# Solder_Training_Tier_3.net
KiCad netlist of a schematic drawn in Altium Designer
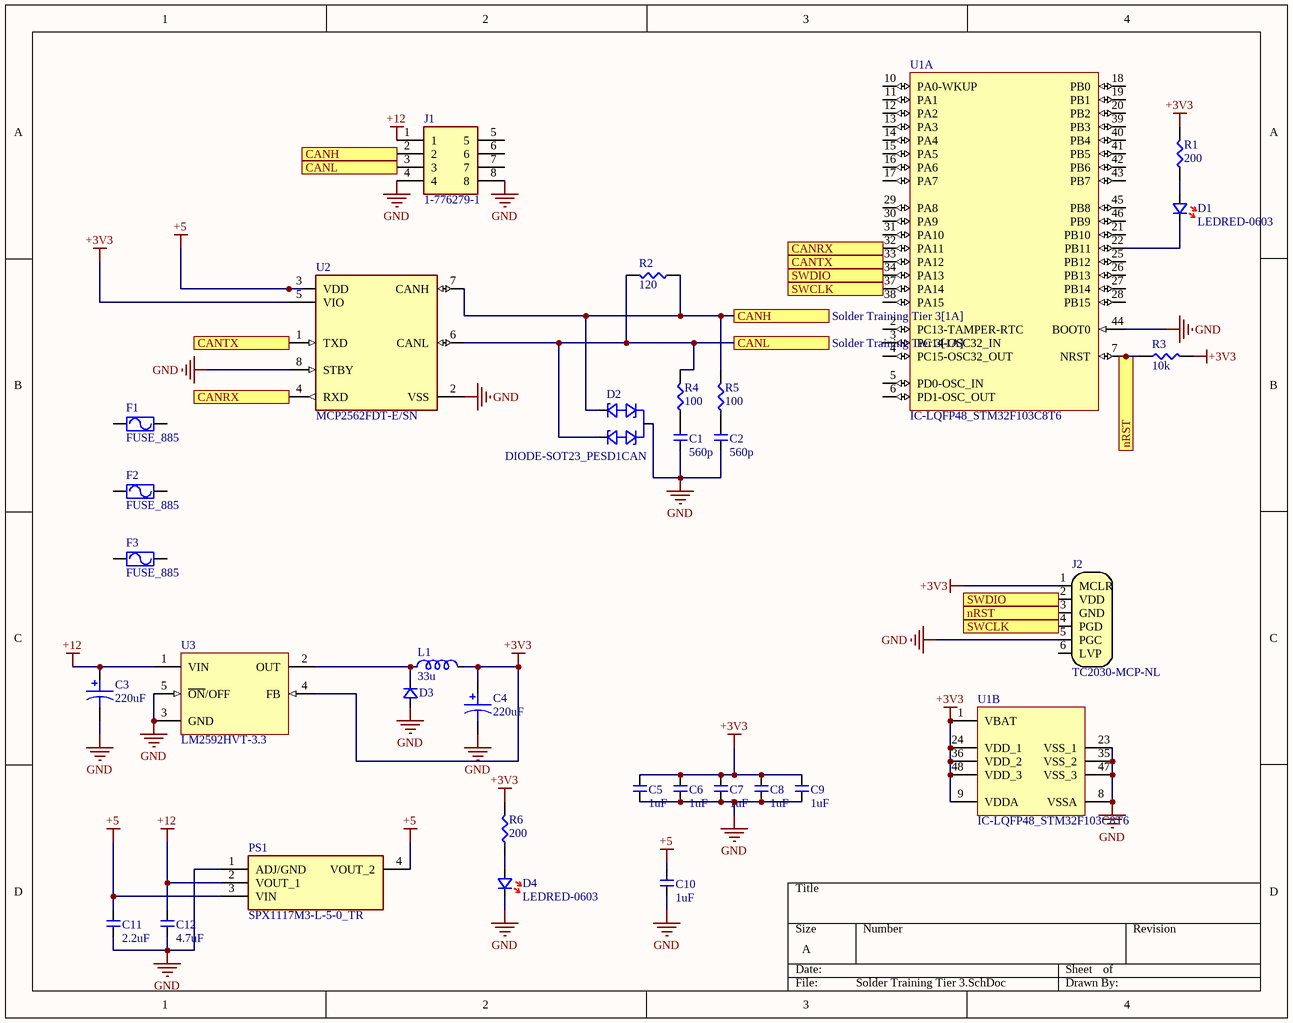
[diagram p0: Solder Training Tier 3.SchDoc]

(export (version "E")
  (design (tool "Eeschema 10.0.6"))
  (components
    (comp (ref "C1")
      (value "560p")
      (footprint "CAP-0603")
      (fields (field (name "SOURCE") "ife19_Elec_Library.SchLib"))
      (libsource (lib "Illini Formula Electric") (part "CAP-0603"))
    )
    (comp (ref "C2")
      (value "560p")
      (footprint "CAP-0603")
      (fields (field (name "SOURCE") "ife19_Elec_Library.SchLib"))
      (libsource (lib "Illini Formula Electric") (part "CAP-0603"))
    )
    (comp (ref "C3")
      (value "220uF")
      (footprint "CAP-6.3D7.7H-SMD")
      (fields (field (name "SOURCE") "ife19_Elec_Library.SchLib"))
      (libsource (lib "Illini Formula Electric") (part "CAP-6.3D7.7H-SMD"))
    )
    (comp (ref "C4")
      (value "220uF")
      (footprint "CAP-6.3D7.7H-SMD")
      (fields (field (name "SOURCE") "ife19_Elec_Library.SchLib"))
      (libsource (lib "Illini Formula Electric") (part "CAP-6.3D7.7H-SMD"))
    )
    (comp (ref "C5")
      (value "1uF")
      (footprint "CAP-0603")
      (fields (field (name "SOURCE") "ife19_Elec_Library.SchLib"))
      (libsource (lib "Illini Formula Electric") (part "CAP-0603"))
    )
    (comp (ref "C6")
      (value "1uF")
      (footprint "CAP-0603")
      (fields (field (name "SOURCE") "ife19_Elec_Library.SchLib"))
      (libsource (lib "Illini Formula Electric") (part "CAP-0603"))
    )
    (comp (ref "C7")
      (value "1uF")
      (footprint "CAP-0603")
      (fields (field (name "SOURCE") "ife19_Elec_Library.SchLib"))
      (libsource (lib "Illini Formula Electric") (part "CAP-0603"))
    )
    (comp (ref "C8")
      (value "1uF")
      (footprint "CAP-0603")
      (fields (field (name "SOURCE") "ife19_Elec_Library.SchLib"))
      (libsource (lib "Illini Formula Electric") (part "CAP-0603"))
    )
    (comp (ref "C9")
      (value "1uF")
      (footprint "CAP-0603")
      (fields (field (name "SOURCE") "ife19_Elec_Library.SchLib"))
      (libsource (lib "Illini Formula Electric") (part "CAP-0603"))
    )
    (comp (ref "C10")
      (value "1uF")
      (footprint "CAP-0603")
      (fields (field (name "SOURCE") "ife19_Elec_Library.SchLib"))
      (libsource (lib "Illini Formula Electric") (part "CAP-0603"))
    )
    (comp (ref "C11")
      (value "2.2uF")
      (footprint "CAP-0603")
      (fields (field (name "SOURCE") "ife19_Elec_Library.SchLib"))
      (libsource (lib "Illini Formula Electric") (part "CAP-0603"))
    )
    (comp (ref "C12")
      (value "4.7uF")
      (footprint "CAP-0603")
      (fields (field (name "SOURCE") "ife19_Elec_Library.SchLib"))
      (libsource (lib "Illini Formula Electric") (part "CAP-0603"))
    )
    (comp (ref "D1")
      (value "LEDRED-0603")
      (footprint "LEDRED-0603")
      (fields (field (name "SOURCE") "ife19_Elec_Library.SchLib"))
      (libsource (lib "") (part "Symbol_3"))
    )
    (comp (ref "D2")
      (value "DIODE-SOT23_PESD1CAN")
      (footprint "SOT23")
      (fields (field (name "SOURCE") "ife19_Elec_Library.SchLib"))
      (libsource (lib "Illini Formula Electric") (part "DIODE-SOT23_PESD1CAN"))
    )
    (comp (ref "D3")
      (value "~")
      (footprint "SOD123")
      (fields (field (name "SOURCE") "ife19_Elec_Library.SchLib"))
      (libsource (lib "") (part "Symbol_4"))
    )
    (comp (ref "D4")
      (value "LEDRED-0603")
      (footprint "LEDRED-0603")
      (fields (field (name "SOURCE") "ife19_Elec_Library.SchLib"))
      (libsource (lib "") (part "Symbol_3"))
    )
    (comp (ref "F1")
      (value "FUSE_885")
      (footprint "FUSE_885")
      (fields (field (name "SOURCE") "ife19_Elec_Library.SchLib"))
      (libsource (lib "") (part "Symbol_1"))
    )
    (comp (ref "F2")
      (value "FUSE_885")
      (footprint "FUSE_885")
      (fields (field (name "SOURCE") "ife19_Elec_Library.SchLib"))
      (libsource (lib "") (part "Symbol_1"))
    )
    (comp (ref "F3")
      (value "FUSE_885")
      (footprint "FUSE_885")
      (fields (field (name "SOURCE") "ife19_Elec_Library.SchLib"))
      (libsource (lib "") (part "Symbol_1"))
    )
    (comp (ref "J1")
      (value "1-776279-1")
      (footprint "17762791")
      (description "Connector")
      (fields (field (name "MOUSER PART NUMBER") "571-1-776279-1"))
      (libsource (lib "Illini Formula Electric") (part "1-776279-1"))
    )
    (comp (ref "J2")
      (value "TC2030-MCP-NL")
      (footprint "TC2030-MCP-NL")
      (description "Conector par ICD")
      (fields (field (name "SOURCE") "Image Pasted at 2021-10-31 17-08.SchLib"))
      (libsource (lib "Illini Formula Electric") (part "TC2030-MCP-NL"))
    )
    (comp (ref "L1")
      (value "33u")
      (footprint "IND-6045")
      (fields (field (name "SOURCE") "ife19_Elec_Library.SchLib"))
      (libsource (lib "Illini Formula Electric") (part "Symbol"))
    )
    (comp (ref "PS1")
      (value "SPX1117M3-L-5-0_TR")
      (footprint "SOT230P700X170-4N")
      (description "Power Supply")
      (fields
        (field (name "ARROW PART NUMBER") "SPX1117M3-L-5-0/TR")
        (field (name "MOUSER PART NUMBER") "701-SPX1117M3-L-50TR")
      )
      (libsource (lib "Illini Formula Electric") (part "SPX1117M3-L-5-0_TR"))
    )
    (comp (ref "R1")
      (value "200")
      (footprint "RES-0603")
      (fields (field (name "SOURCE") "ife19_Elec_Library.SchLib"))
      (libsource (lib "") (part "Symbol_2"))
    )
    (comp (ref "R2")
      (value "120")
      (footprint "RES-0603")
      (fields (field (name "SOURCE") "ife19_Elec_Library.SchLib"))
      (libsource (lib "") (part "Symbol_2"))
    )
    (comp (ref "R3")
      (value "10k")
      (footprint "RES-0603")
      (fields (field (name "SOURCE") "ife19_Elec_Library.schlib"))
      (libsource (lib "") (part "Symbol_2"))
    )
    (comp (ref "R4")
      (value "100")
      (footprint "RES-0603")
      (fields (field (name "SOURCE") "ife19_Elec_Library.SchLib"))
      (libsource (lib "") (part "Symbol_2"))
    )
    (comp (ref "R5")
      (value "100")
      (footprint "RES-0603")
      (fields (field (name "SOURCE") "ife19_Elec_Library.SchLib"))
      (libsource (lib "") (part "Symbol_2"))
    )
    (comp (ref "R6")
      (value "200")
      (footprint "RES-0603")
      (fields (field (name "SOURCE") "ife19_Elec_Library.SchLib"))
      (libsource (lib "") (part "Symbol_2"))
    )
    (comp (ref "U1")
      (value "IC-LQFP48_STM32F103C8T6")
      (footprint "STM-LQFP48_M")
      (fields (field (name "PARTNUMBER") "STM32F103C8T6") (field (name "SOURCE") "ife19_Elec_Library.SchLib"))
      (libsource (lib "Illini Formula Electric") (part "IC-LQFP48_STM32F103C8T6"))
    )
    (comp (ref "U2")
      (value "MCP2562FDT-E/SN")
      (footprint "FP-C04-057-SN-MFG")
      (description "IC TRANSCEIVER 1/1 8SOIC")
      (libsource (lib "Altium Content Vault") (part "fcb6c66e4429206983adab9201371df"))
    )
    (comp (ref "U3")
      (value "LM2592HVT-3.3")
      (footprint "T05D")
      (description "SIMPLE SWITCHER® Power Converter 150 KHz 2A Step-Down Voltage Regulator, 5-pin TO-220")
      (fields (field (name "MANUFACTURER") "National Semiconductor"))
      (libsource (lib "Altium Content Vault") (part "PM-REG-LM2575HVT-12"))
    )
  )
  (nets
    (net (code "1") (name "+3V3") (class "Default")
      (node (ref "C4") (pin "POS") (pinfunction "+_POS") (pintype "passive"))
      (node (ref "C5") (pin "2") (pinfunction "2_2") (pintype "passive"))
      (node (ref "C6") (pin "2") (pinfunction "2_2") (pintype "passive"))
      (node (ref "C7") (pin "2") (pinfunction "2_2") (pintype "passive"))
      (node (ref "C8") (pin "2") (pinfunction "2_2") (pintype "passive"))
      (node (ref "C9") (pin "2") (pinfunction "2_2") (pintype "passive"))
      (node (ref "J2") (pin "1") (pinfunction "MCLR_1") (pintype "passive"))
      (node (ref "L1") (pin "2") (pinfunction "2_2") (pintype "passive"))
      (node (ref "R1") (pin "2") (pinfunction "2_2") (pintype "passive"))
      (node (ref "R3") (pin "2") (pinfunction "2_2") (pintype "passive"))
      (node (ref "R6") (pin "2") (pinfunction "2_2") (pintype "passive"))
      (node (ref "U1") (pin "1") (pinfunction "VBAT_1") (pintype "power_in"))
      (node (ref "U1") (pin "24") (pinfunction "VDD_1_24") (pintype "power_in"))
      (node (ref "U1") (pin "36") (pinfunction "VDD_2_36") (pintype "power_in"))
      (node (ref "U1") (pin "48") (pinfunction "VDD_3_48") (pintype "power_in"))
      (node (ref "U1") (pin "9") (pinfunction "VDDA_9") (pintype "power_in"))
      (node (ref "U2") (pin "5") (pinfunction "VIO_5") (pintype "power_in"))
      (node (ref "U3") (pin "4") (pinfunction "FB_4") (pintype "input"))
    )
    (net (code "2") (name "+5") (class "Default")
      (node (ref "C10") (pin "2") (pinfunction "2_2") (pintype "passive"))
      (node (ref "C11") (pin "2") (pinfunction "2_2") (pintype "passive"))
      (node (ref "PS1") (pin "3") (pinfunction "VIN_3") (pintype "passive"))
      (node (ref "PS1") (pin "4") (pinfunction "VOUT_2_4") (pintype "passive"))
      (node (ref "U2") (pin "3") (pinfunction "VDD_3") (pintype "power_in"))
    )
    (net (code "3") (name "+12") (class "Default")
      (node (ref "C12") (pin "2") (pinfunction "2_2") (pintype "passive"))
      (node (ref "C3") (pin "POS") (pinfunction "+_POS") (pintype "passive"))
      (node (ref "J1") (pin "1") (pinfunction "1_1") (pintype "passive"))
      (node (ref "PS1") (pin "2") (pinfunction "VOUT_1_2") (pintype "passive"))
      (node (ref "U3") (pin "1") (pinfunction "VIN_1") (pintype "power_in"))
    )
    (net (code "4") (name "/CANH") (class "Default")
      (node (ref "D2") (pin "1") (pinfunction "CAN1_1") (pintype "passive"))
      (node (ref "J1") (pin "2") (pinfunction "2_2") (pintype "passive"))
      (node (ref "R2") (pin "1") (pinfunction "1_1") (pintype "passive"))
      (node (ref "R5") (pin "2") (pinfunction "2_2") (pintype "passive"))
      (node (ref "U2") (pin "7") (pinfunction "CANH_7") (pintype "bidirectional"))
    )
    (net (code "5") (name "/CANL") (class "Default")
      (node (ref "D2") (pin "2") (pinfunction "CAN2_2") (pintype "passive"))
      (node (ref "J1") (pin "3") (pinfunction "3_3") (pintype "passive"))
      (node (ref "R2") (pin "2") (pinfunction "2_2") (pintype "passive"))
      (node (ref "R4") (pin "2") (pinfunction "2_2") (pintype "passive"))
      (node (ref "U2") (pin "6") (pinfunction "CANL_6") (pintype "bidirectional"))
    )
    (net (code "6") (name "/CANRX") (class "Default")
      (node (ref "U1") (pin "32") (pinfunction "PA11_32") (pintype "bidirectional"))
      (node (ref "U2") (pin "4") (pinfunction "RXD_4") (pintype "output"))
    )
    (net (code "7") (name "/CANTX") (class "Default")
      (node (ref "U1") (pin "33") (pinfunction "PA12_33") (pintype "bidirectional"))
      (node (ref "U2") (pin "1") (pinfunction "TXD_1") (pintype "input"))
    )
    (net (code "8") (name "/SWCLK") (class "Default")
      (node (ref "J2") (pin "4") (pinfunction "PGD_4") (pintype "passive"))
      (node (ref "U1") (pin "37") (pinfunction "PA14_37") (pintype "bidirectional"))
    )
    (net (code "9") (name "/SWDIO") (class "Default")
      (node (ref "J2") (pin "2") (pinfunction "VDD_2") (pintype "passive"))
      (node (ref "U1") (pin "34") (pinfunction "PA13_34") (pintype "bidirectional"))
    )
    (net (code "10") (name "/nRST") (class "Default")
      (node (ref "J2") (pin "3") (pinfunction "GND_3") (pintype "passive"))
      (node (ref "R3") (pin "1") (pinfunction "1_1") (pintype "passive"))
      (node (ref "U1") (pin "7") (pinfunction "NRST_7") (pintype "bidirectional"))
    )
    (net (code "11") (name "GND") (class "Default")
      (node (ref "C1") (pin "1") (pinfunction "1_1") (pintype "passive"))
      (node (ref "C10") (pin "1") (pinfunction "1_1") (pintype "passive"))
      (node (ref "C11") (pin "1") (pinfunction "1_1") (pintype "passive"))
      (node (ref "C12") (pin "1") (pinfunction "1_1") (pintype "passive"))
      (node (ref "C2") (pin "1") (pinfunction "1_1") (pintype "passive"))
      (node (ref "C3") (pin "NEG") (pinfunction "-_NEG") (pintype "passive"))
      (node (ref "C4") (pin "NEG") (pinfunction "-_NEG") (pintype "passive"))
      (node (ref "C5") (pin "1") (pinfunction "1_1") (pintype "passive"))
      (node (ref "C6") (pin "1") (pinfunction "1_1") (pintype "passive"))
      (node (ref "C7") (pin "1") (pinfunction "1_1") (pintype "passive"))
      (node (ref "C8") (pin "1") (pinfunction "1_1") (pintype "passive"))
      (node (ref "C9") (pin "1") (pinfunction "1_1") (pintype "passive"))
      (node (ref "D2") (pin "3") (pinfunction "G_3") (pintype "passive"))
      (node (ref "D3") (pin "A") (pinfunction "A_A") (pintype "passive"))
      (node (ref "D4") (pin "K") (pinfunction "K_K") (pintype "passive"))
      (node (ref "J1") (pin "4") (pinfunction "4_4") (pintype "passive"))
      (node (ref "J1") (pin "8") (pinfunction "8_8") (pintype "passive"))
      (node (ref "J2") (pin "5") (pinfunction "PGC_5") (pintype "passive"))
      (node (ref "PS1") (pin "1") (pinfunction "ADJ/GND_1") (pintype "passive"))
      (node (ref "U1") (pin "23") (pinfunction "VSS_1_23") (pintype "power_in"))
      (node (ref "U1") (pin "35") (pinfunction "VSS_2_35") (pintype "power_in"))
      (node (ref "U1") (pin "44") (pinfunction "BOOT0_44") (pintype "input"))
      (node (ref "U1") (pin "47") (pinfunction "VSS_3_47") (pintype "power_in"))
      (node (ref "U1") (pin "8") (pinfunction "VSSA_8") (pintype "power_in"))
      (node (ref "U2") (pin "2") (pinfunction "VSS_2") (pintype "power_in"))
      (node (ref "U2") (pin "8") (pinfunction "STBY_8") (pintype "input"))
      (node (ref "U3") (pin "3") (pinfunction "GND_3") (pintype "power_in"))
      (node (ref "U3") (pin "5") (pinfunction "~{ON}/OFF_5") (pintype "input"))
    )
    (net (code "12") (name "Net-(C1-Pad2)") (class "Default")
      (node (ref "C1") (pin "2") (pinfunction "2_2") (pintype "passive"))
      (node (ref "R4") (pin "1") (pinfunction "1_1") (pintype "passive"))
    )
    (net (code "13") (name "Net-(C2-Pad2)") (class "Default")
      (node (ref "C2") (pin "2") (pinfunction "2_2") (pintype "passive"))
      (node (ref "R5") (pin "1") (pinfunction "1_1") (pintype "passive"))
    )
    (net (code "14") (name "Net-(D1-PadA)") (class "Default")
      (node (ref "D1") (pin "A") (pinfunction "A_A") (pintype "passive"))
      (node (ref "R1") (pin "1") (pinfunction "1_1") (pintype "passive"))
    )
    (net (code "15") (name "Net-(D4-PadA)") (class "Default")
      (node (ref "D4") (pin "A") (pinfunction "A_A") (pintype "passive"))
      (node (ref "R6") (pin "1") (pinfunction "1_1") (pintype "passive"))
    )
    (net (code "16") (name "Net-(U1A-PB11)") (class "Default")
      (node (ref "D1") (pin "K") (pinfunction "K_K") (pintype "passive"))
      (node (ref "U1") (pin "22") (pinfunction "PB11_22") (pintype "bidirectional"))
    )
    (net (code "17") (name "Net-(U3-OUT)") (class "Default")
      (node (ref "D3") (pin "K") (pinfunction "K_K") (pintype "passive"))
      (node (ref "L1") (pin "1") (pinfunction "1_1") (pintype "passive"))
      (node (ref "U3") (pin "2") (pinfunction "OUT_2") (pintype "power_in"))
    )
    (net (code "18") (name "unconnected-(F1-Pad1)") (class "Default")
      (node (ref "F1") (pin "1") (pinfunction "1_1") (pintype "passive"))
    )
    (net (code "19") (name "unconnected-(F1-Pad2)") (class "Default")
      (node (ref "F1") (pin "2") (pinfunction "2_2") (pintype "passive"))
    )
    (net (code "20") (name "unconnected-(F2-Pad1)") (class "Default")
      (node (ref "F2") (pin "1") (pinfunction "1_1") (pintype "passive"))
    )
    (net (code "21") (name "unconnected-(F2-Pad2)") (class "Default")
      (node (ref "F2") (pin "2") (pinfunction "2_2") (pintype "passive"))
    )
    (net (code "22") (name "unconnected-(F3-Pad1)") (class "Default")
      (node (ref "F3") (pin "1") (pinfunction "1_1") (pintype "passive"))
    )
    (net (code "23") (name "unconnected-(F3-Pad2)") (class "Default")
      (node (ref "F3") (pin "2") (pinfunction "2_2") (pintype "passive"))
    )
    (net (code "24") (name "unconnected-(J1-Pad5)") (class "Default")
      (node (ref "J1") (pin "5") (pinfunction "5_5") (pintype "passive"))
    )
    (net (code "25") (name "unconnected-(J1-Pad6)") (class "Default")
      (node (ref "J1") (pin "6") (pinfunction "6_6") (pintype "passive"))
    )
    (net (code "26") (name "unconnected-(J1-Pad7)") (class "Default")
      (node (ref "J1") (pin "7") (pinfunction "7_7") (pintype "passive"))
    )
    (net (code "27") (name "unconnected-(J2-LVP-Pad6)") (class "Default")
      (node (ref "J2") (pin "6") (pinfunction "LVP_6") (pintype "passive"))
    )
    (net (code "28") (name "unconnected-(U1A-PA0-WKUP-Pad10)") (class "Default")
      (node (ref "U1") (pin "10") (pinfunction "PA0-WKUP_10") (pintype "bidirectional"))
    )
    (net (code "29") (name "unconnected-(U1A-PA1-Pad11)") (class "Default")
      (node (ref "U1") (pin "11") (pinfunction "PA1_11") (pintype "bidirectional"))
    )
    (net (code "30") (name "unconnected-(U1A-PA2-Pad12)") (class "Default")
      (node (ref "U1") (pin "12") (pinfunction "PA2_12") (pintype "bidirectional"))
    )
    (net (code "31") (name "unconnected-(U1A-PA3-Pad13)") (class "Default")
      (node (ref "U1") (pin "13") (pinfunction "PA3_13") (pintype "bidirectional"))
    )
    (net (code "32") (name "unconnected-(U1A-PA4-Pad14)") (class "Default")
      (node (ref "U1") (pin "14") (pinfunction "PA4_14") (pintype "bidirectional"))
    )
    (net (code "33") (name "unconnected-(U1A-PA5-Pad15)") (class "Default")
      (node (ref "U1") (pin "15") (pinfunction "PA5_15") (pintype "bidirectional"))
    )
    (net (code "34") (name "unconnected-(U1A-PA6-Pad16)") (class "Default")
      (node (ref "U1") (pin "16") (pinfunction "PA6_16") (pintype "bidirectional"))
    )
    (net (code "35") (name "unconnected-(U1A-PA7-Pad17)") (class "Default")
      (node (ref "U1") (pin "17") (pinfunction "PA7_17") (pintype "bidirectional"))
    )
    (net (code "36") (name "unconnected-(U1A-PA8-Pad29)") (class "Default")
      (node (ref "U1") (pin "29") (pinfunction "PA8_29") (pintype "bidirectional"))
    )
    (net (code "37") (name "unconnected-(U1A-PA9-Pad30)") (class "Default")
      (node (ref "U1") (pin "30") (pinfunction "PA9_30") (pintype "bidirectional"))
    )
    (net (code "38") (name "unconnected-(U1A-PA10-Pad31)") (class "Default")
      (node (ref "U1") (pin "31") (pinfunction "PA10_31") (pintype "bidirectional"))
    )
    (net (code "39") (name "unconnected-(U1A-PA15-Pad38)") (class "Default")
      (node (ref "U1") (pin "38") (pinfunction "PA15_38") (pintype "bidirectional"))
    )
    (net (code "40") (name "unconnected-(U1A-PB0-Pad18)") (class "Default")
      (node (ref "U1") (pin "18") (pinfunction "PB0_18") (pintype "bidirectional"))
    )
    (net (code "41") (name "unconnected-(U1A-PB1-Pad19)") (class "Default")
      (node (ref "U1") (pin "19") (pinfunction "PB1_19") (pintype "bidirectional"))
    )
    (net (code "42") (name "unconnected-(U1A-PB2-Pad20)") (class "Default")
      (node (ref "U1") (pin "20") (pinfunction "PB2_20") (pintype "bidirectional"))
    )
    (net (code "43") (name "unconnected-(U1A-PB3-Pad39)") (class "Default")
      (node (ref "U1") (pin "39") (pinfunction "PB3_39") (pintype "bidirectional"))
    )
    (net (code "44") (name "unconnected-(U1A-PB4-Pad40)") (class "Default")
      (node (ref "U1") (pin "40") (pinfunction "PB4_40") (pintype "bidirectional"))
    )
    (net (code "45") (name "unconnected-(U1A-PB5-Pad41)") (class "Default")
      (node (ref "U1") (pin "41") (pinfunction "PB5_41") (pintype "bidirectional"))
    )
    (net (code "46") (name "unconnected-(U1A-PB6-Pad42)") (class "Default")
      (node (ref "U1") (pin "42") (pinfunction "PB6_42") (pintype "bidirectional"))
    )
    (net (code "47") (name "unconnected-(U1A-PB7-Pad43)") (class "Default")
      (node (ref "U1") (pin "43") (pinfunction "PB7_43") (pintype "bidirectional"))
    )
    (net (code "48") (name "unconnected-(U1A-PB8-Pad45)") (class "Default")
      (node (ref "U1") (pin "45") (pinfunction "PB8_45") (pintype "bidirectional"))
    )
    (net (code "49") (name "unconnected-(U1A-PB9-Pad46)") (class "Default")
      (node (ref "U1") (pin "46") (pinfunction "PB9_46") (pintype "bidirectional"))
    )
    (net (code "50") (name "unconnected-(U1A-PB10-Pad21)") (class "Default")
      (node (ref "U1") (pin "21") (pinfunction "PB10_21") (pintype "bidirectional"))
    )
    (net (code "51") (name "unconnected-(U1A-PB12-Pad25)") (class "Default")
      (node (ref "U1") (pin "25") (pinfunction "PB12_25") (pintype "bidirectional"))
    )
    (net (code "52") (name "unconnected-(U1A-PB13-Pad26)") (class "Default")
      (node (ref "U1") (pin "26") (pinfunction "PB13_26") (pintype "bidirectional"))
    )
    (net (code "53") (name "unconnected-(U1A-PB14-Pad27)") (class "Default")
      (node (ref "U1") (pin "27") (pinfunction "PB14_27") (pintype "bidirectional"))
    )
    (net (code "54") (name "unconnected-(U1A-PB15-Pad28)") (class "Default")
      (node (ref "U1") (pin "28") (pinfunction "PB15_28") (pintype "bidirectional"))
    )
    (net (code "55") (name "unconnected-(U1A-PC13-TAMPER-RTC-Pad2)") (class "Default")
      (node (ref "U1") (pin "2") (pinfunction "PC13-TAMPER-RTC_2") (pintype "bidirectional"))
    )
    (net (code "56") (name "unconnected-(U1A-PC14-OSC32_IN-Pad3)") (class "Default")
      (node (ref "U1") (pin "3") (pinfunction "PC14-OSC32_IN_3") (pintype "bidirectional"))
    )
    (net (code "57") (name "unconnected-(U1A-PC15-OSC32_OUT-Pad4)") (class "Default")
      (node (ref "U1") (pin "4") (pinfunction "PC15-OSC32_OUT_4") (pintype "bidirectional"))
    )
    (net (code "58") (name "unconnected-(U1A-PD0-OSC_IN-Pad5)") (class "Default")
      (node (ref "U1") (pin "5") (pinfunction "PD0-OSC_IN_5") (pintype "bidirectional"))
    )
    (net (code "59") (name "unconnected-(U1A-PD1-OSC_OUT-Pad6)") (class "Default")
      (node (ref "U1") (pin "6") (pinfunction "PD1-OSC_OUT_6") (pintype "bidirectional"))
    )
  )
)
